# ALSN_v2.net
KiCad netlist of a schematic drawn in EAGLE
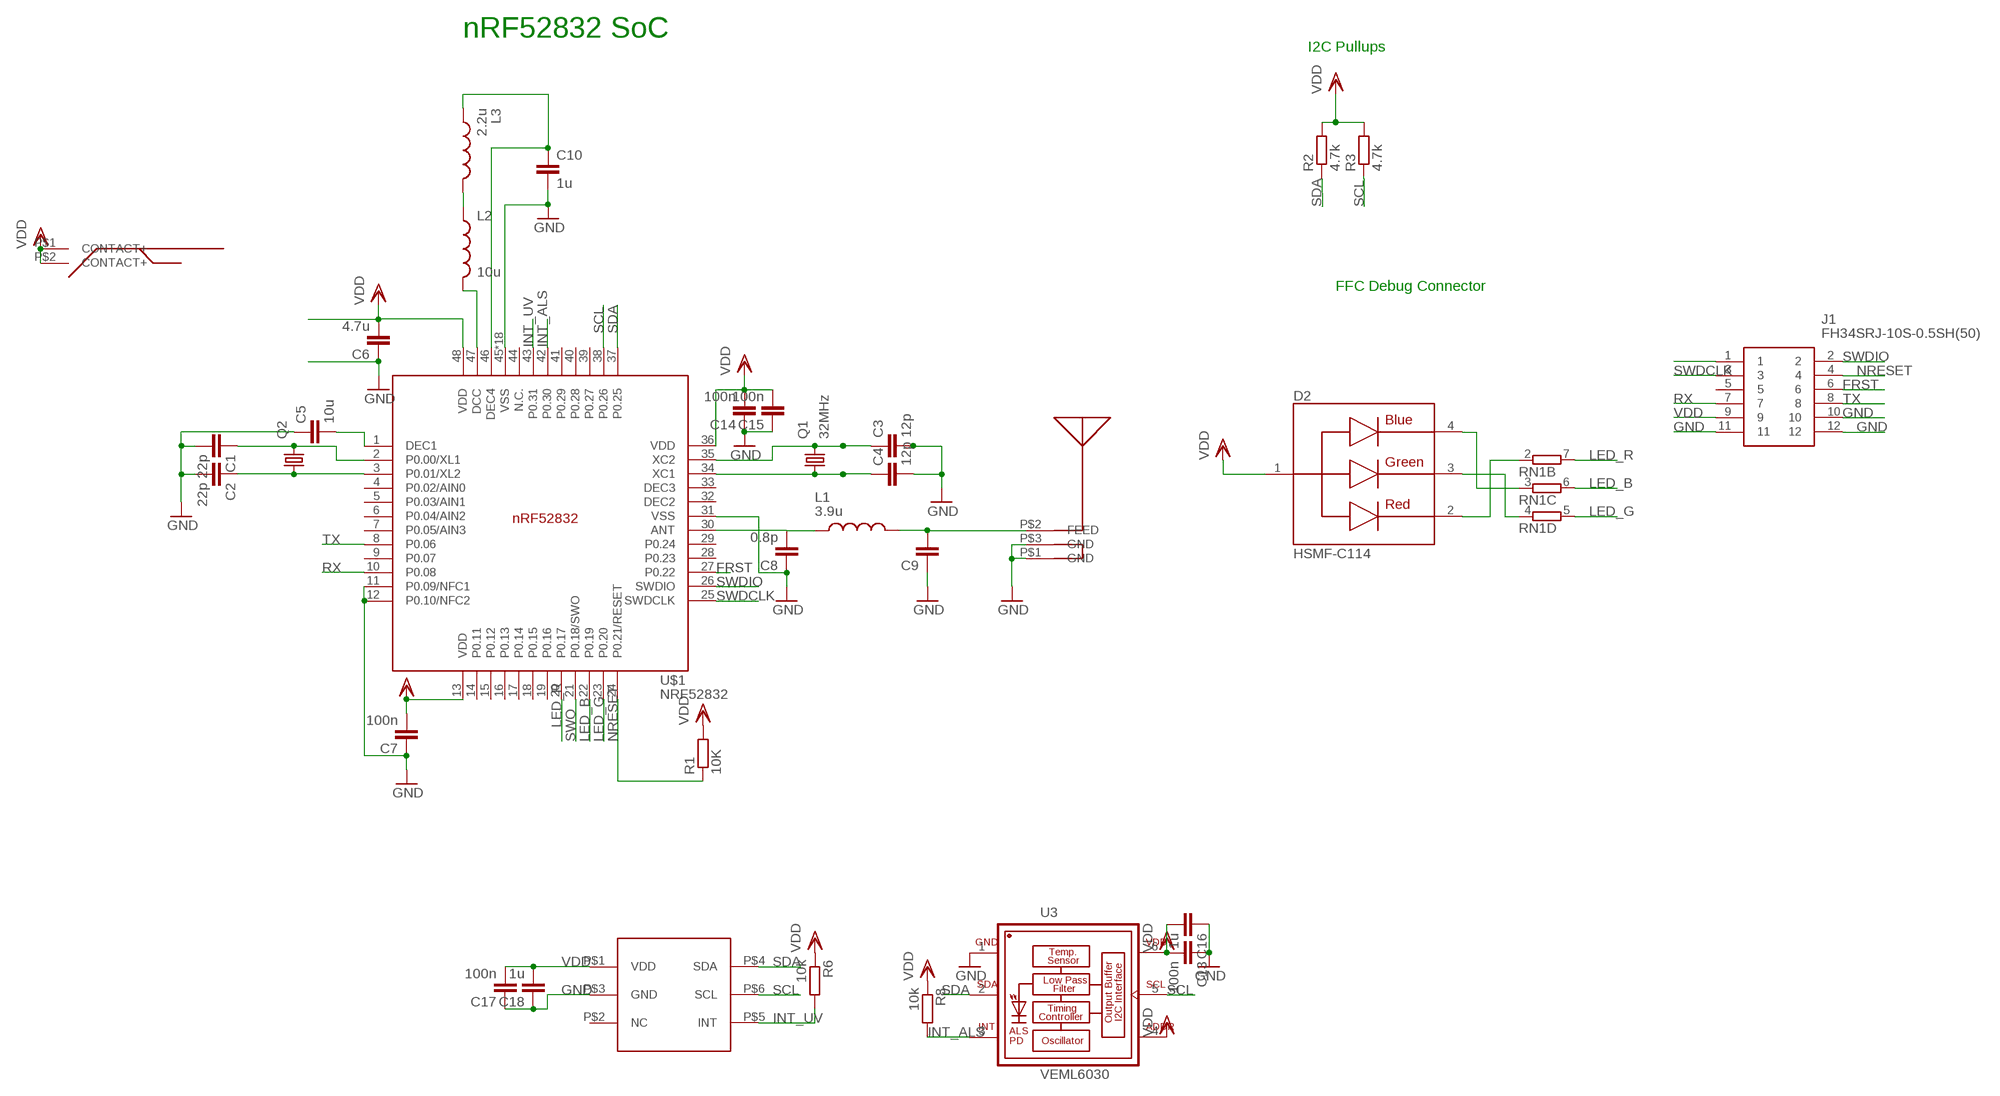
[diagram p0: schematic, sheet 1]

(export (version "E")
  (design (tool "Eeschema 10.0.6"))
  (components
    (comp (ref "C1")
      (value "22p")
      (footprint "eagle-import:C0402")
      (libsource (lib "eagle-import") (part "CC0402"))
    )
    (comp (ref "C2")
      (value "22p")
      (footprint "eagle-import:C0402")
      (libsource (lib "eagle-import") (part "CC0402"))
    )
    (comp (ref "C3")
      (value "12p")
      (footprint "eagle-import:C0402")
      (libsource (lib "eagle-import") (part "CC0402"))
    )
    (comp (ref "C4")
      (value "12p")
      (footprint "eagle-import:C0402")
      (libsource (lib "eagle-import") (part "CC0402"))
    )
    (comp (ref "C5")
      (value "10u")
      (footprint "eagle-import:C0402")
      (libsource (lib "eagle-import") (part "CC0402"))
    )
    (comp (ref "C6")
      (value "4.7u")
      (footprint "eagle-import:C0402")
      (libsource (lib "eagle-import") (part "CC0402"))
    )
    (comp (ref "C7")
      (value "100n")
      (footprint "eagle-import:C0603R")
      (libsource (lib "eagle-import") (part "CC0603R"))
    )
    (comp (ref "C8")
      (value "0.8p")
      (footprint "eagle-import:C0402")
      (libsource (lib "eagle-import") (part "CC0402"))
    )
    (comp (ref "C9")
      (value "1.2p")
      (footprint "eagle-import:C0402")
      (libsource (lib "eagle-import") (part "CC0402"))
    )
    (comp (ref "C10")
      (value "1u")
      (footprint "eagle-import:C0402")
      (libsource (lib "eagle-import") (part "CC0402"))
    )
    (comp (ref "C13")
      (value "100n")
      (footprint "eagle-import:C0402")
      (libsource (lib "eagle-import") (part "CC0402"))
    )
    (comp (ref "C14")
      (value "100n")
      (footprint "eagle-import:C0402")
      (libsource (lib "eagle-import") (part "CC0402"))
    )
    (comp (ref "C15")
      (value "100n")
      (footprint "eagle-import:C0402")
      (libsource (lib "eagle-import") (part "CC0402"))
    )
    (comp (ref "C16")
      (value "1u")
      (footprint "eagle-import:C0402")
      (libsource (lib "eagle-import") (part "CC0402"))
    )
    (comp (ref "C17")
      (value "100n")
      (footprint "eagle-import:C0402")
      (libsource (lib "eagle-import") (part "CC0402"))
    )
    (comp (ref "C18")
      (value "1u")
      (footprint "eagle-import:C0402")
      (libsource (lib "eagle-import") (part "CC0402"))
    )
    (comp (ref "D2")
      (value "HSMF-C114")
      (footprint "eagle-import:DIOSC160X150X35-4N")
      (fields (field (name "MF") "Broadcom Limited"))
      (libsource (lib "eagle-import") (part "HSMF-C114"))
    )
    (comp (ref "J1")
      (value "FH34SRJ-10S-0.5SH(50)")
      (footprint "eagle-import:FH34SRJ10S05SH50")
      (fields (field (name "MF") "Hirose Connector"))
      (libsource (lib "eagle-import") (part "FH34SRJ-10S-0.5SH(50)"))
    )
    (comp (ref "L1")
      (value "3.9u")
      (footprint "eagle-import:INDC0402X26N")
      (fields (field (name "MF") "TDK") (field (name "MP") "MHQ0402P7N5JT000"))
      (libsource (lib "eagle-import") (part "MHQ0402P7N5JT000"))
    )
    (comp (ref "L2")
      (value "10u")
      (footprint "eagle-import:L0603")
      (libsource (lib "eagle-import") (part "INDUCTOR"))
    )
    (comp (ref "L3")
      (value "2.2u")
      (footprint "eagle-import:INDC0402X26N")
      (fields (field (name "MF") "TDK") (field (name "MP") "MHQ0402P7N5JT000"))
      (libsource (lib "eagle-import") (part "MHQ0402P7N5JT000"))
    )
    (comp (ref "Q1")
      (value "32MHz")
      (footprint "eagle-import:2.0X1.6_KX-5")
      (libsource (lib "eagle-import") (part "KX-5"))
    )
    (comp (ref "Q2")
      (value "KX-327-RT")
      (footprint "eagle-import:2.0X1.2")
      (libsource (lib "eagle-import") (part "KX-327-RT"))
    )
    (comp (ref "R1")
      (value "10K")
      (footprint "eagle-import:R0402")
      (libsource (lib "eagle-import") (part "RR0402"))
    )
    (comp (ref "R2")
      (value "4.7k")
      (footprint "eagle-import:R0402")
      (libsource (lib "eagle-import") (part "RR0402"))
    )
    (comp (ref "R3")
      (value "4.7k")
      (footprint "eagle-import:R0402")
      (libsource (lib "eagle-import") (part "RR0402"))
    )
    (comp (ref "R6")
      (value "10k")
      (footprint "eagle-import:R0402")
      (libsource (lib "eagle-import") (part "RR0402"))
    )
    (comp (ref "R8")
      (value "10k")
      (footprint "eagle-import:R0402")
      (libsource (lib "eagle-import") (part "RR0402"))
    )
    (comp (ref "RN1")
      (value "4R-N0402ARV341")
      (footprint "eagle-import:4X0402ARV341")
      (libsource (lib "eagle-import") (part "4R-N0402ARV341"))
    )
    (comp (ref "U$1")
      (value "NRF52832")
      (footprint "eagle-import:QFN40P600X600X90-48_N")
      (libsource (lib "eagle-import") (part "NRF52832"))
    )
    (comp (ref "U$2")
      (value "CR2032-THT")
      (footprint "eagle-import:CR2032-THT")
      (libsource (lib "eagle-import") (part "CR2032-THT"))
    )
    (comp (ref "U$3")
      (value "LTR-390UV")
      (footprint "eagle-import:LTR-390UV")
      (libsource (lib "eagle-import") (part "LTR-390UV"))
    )
    (comp (ref "U$4")
      (value "CHIPANTENNAL2")
      (footprint "eagle-import:CHIPANTENNAL2")
      (libsource (lib "eagle-import") (part "CHIPANTENNAL2"))
    )
    (comp (ref "U3")
      (value "VEML6030")
      (footprint "eagle-import:VISHAY_VEML6030_2X2X0.87")
      (fields (field (name "MF") "Vishay"))
      (libsource (lib "eagle-import") (part "VEML6030"))
    )
  )
  (nets
    (net (code "1") (name "/FRST") (class "Default")
      (node (ref "J1") (pin "6") (pinfunction "6_6") (pintype "bidirectional"))
      (node (ref "U$1") (pin "27") (pinfunction "P0.22_27") (pintype "bidirectional"))
    )
    (net (code "2") (name "/INT_ALS") (class "Default")
      (node (ref "R8") (pin "2") (pinfunction "2_2") (pintype "passive"))
      (node (ref "U$1") (pin "42") (pinfunction "P0.30_42") (pintype "bidirectional"))
      (node (ref "U3") (pin "3") (pinfunction "INT_3") (pintype "output"))
    )
    (net (code "3") (name "/INT_UV") (class "Default")
      (node (ref "R6") (pin "2") (pinfunction "2_2") (pintype "passive"))
      (node (ref "U$1") (pin "43") (pinfunction "P0.31_43") (pintype "bidirectional"))
      (node (ref "U$3") (pin "P$5") (pinfunction "INT_P$5") (pintype "bidirectional"))
    )
    (net (code "4") (name "/LED_B") (class "Default")
      (node (ref "RN1") (pin "6") (pinfunction "2_6") (pintype "passive"))
      (node (ref "U$1") (pin "22") (pinfunction "P0.19_22") (pintype "bidirectional"))
    )
    (net (code "5") (name "/LED_G") (class "Default")
      (node (ref "RN1") (pin "5") (pinfunction "2_5") (pintype "passive"))
      (node (ref "U$1") (pin "23") (pinfunction "P0.20_23") (pintype "bidirectional"))
    )
    (net (code "6") (name "/LED_R") (class "Default")
      (node (ref "RN1") (pin "7") (pinfunction "2_7") (pintype "passive"))
      (node (ref "U$1") (pin "20") (pinfunction "P0.17_20") (pintype "bidirectional"))
    )
    (net (code "7") (name "/NRESET") (class "Default")
      (node (ref "J1") (pin "4") (pinfunction "4_4") (pintype "bidirectional"))
      (node (ref "R1") (pin "1") (pinfunction "1_1") (pintype "passive"))
      (node (ref "U$1") (pin "24") (pinfunction "P0.21/RESET_24") (pintype "bidirectional"))
    )
    (net (code "8") (name "/RX") (class "Default")
      (node (ref "J1") (pin "7") (pinfunction "7_7") (pintype "bidirectional"))
      (node (ref "U$1") (pin "10") (pinfunction "P0.08_10") (pintype "bidirectional"))
    )
    (net (code "9") (name "/SCL") (class "Default")
      (node (ref "R3") (pin "1") (pinfunction "1_1") (pintype "passive"))
      (node (ref "U$1") (pin "38") (pinfunction "P0.26_38") (pintype "bidirectional"))
      (node (ref "U$3") (pin "P$6") (pinfunction "SCL_P$6") (pintype "bidirectional"))
      (node (ref "U3") (pin "5") (pinfunction "SCL_5") (pintype "input"))
    )
    (net (code "10") (name "/SDA") (class "Default")
      (node (ref "R2") (pin "1") (pinfunction "1_1") (pintype "passive"))
      (node (ref "U$1") (pin "37") (pinfunction "P0.25_37") (pintype "bidirectional"))
      (node (ref "U$3") (pin "P$4") (pinfunction "SDA_P$4") (pintype "bidirectional"))
      (node (ref "U3") (pin "2") (pinfunction "SDA_2") (pintype "bidirectional"))
    )
    (net (code "11") (name "/SWDCLK") (class "Default")
      (node (ref "J1") (pin "3") (pinfunction "3_3") (pintype "bidirectional"))
      (node (ref "U$1") (pin "25") (pinfunction "SWDCLK_25") (pintype "input"))
    )
    (net (code "12") (name "/SWDIO") (class "Default")
      (node (ref "J1") (pin "2") (pinfunction "2_2") (pintype "bidirectional"))
      (node (ref "U$1") (pin "26") (pinfunction "SWDIO_26") (pintype "bidirectional"))
    )
    (net (code "13") (name "/SWO") (class "Default")
      (node (ref "U$1") (pin "21") (pinfunction "P0.18/SWO_21") (pintype "bidirectional"))
    )
    (net (code "14") (name "/TX") (class "Default")
      (node (ref "J1") (pin "8") (pinfunction "8_8") (pintype "bidirectional"))
      (node (ref "U$1") (pin "8") (pinfunction "P0.06_8") (pintype "bidirectional"))
    )
    (net (code "15") (name "GND") (class "Default")
      (node (ref "C1") (pin "2") (pinfunction "2_2") (pintype "passive"))
      (node (ref "C10") (pin "2") (pinfunction "2_2") (pintype "passive"))
      (node (ref "C13") (pin "1") (pinfunction "1_1") (pintype "passive"))
      (node (ref "C14") (pin "1") (pinfunction "1_1") (pintype "passive"))
      (node (ref "C15") (pin "1") (pinfunction "1_1") (pintype "passive"))
      (node (ref "C16") (pin "1") (pinfunction "1_1") (pintype "passive"))
      (node (ref "C17") (pin "1") (pinfunction "1_1") (pintype "passive"))
      (node (ref "C18") (pin "1") (pinfunction "1_1") (pintype "passive"))
      (node (ref "C2") (pin "2") (pinfunction "2_2") (pintype "passive"))
      (node (ref "C3") (pin "2") (pinfunction "2_2") (pintype "passive"))
      (node (ref "C4") (pin "2") (pinfunction "2_2") (pintype "passive"))
      (node (ref "C5") (pin "1") (pinfunction "1_1") (pintype "passive"))
      (node (ref "C6") (pin "1") (pinfunction "1_1") (pintype "passive"))
      (node (ref "C7") (pin "1") (pinfunction "1_1") (pintype "passive"))
      (node (ref "C8") (pin "1") (pinfunction "1_1") (pintype "passive"))
      (node (ref "C9") (pin "1") (pinfunction "1_1") (pintype "passive"))
      (node (ref "J1") (pin "10") (pinfunction "10_10") (pintype "bidirectional"))
      (node (ref "J1") (pin "11") (pinfunction "11_11") (pintype "bidirectional"))
      (node (ref "J1") (pin "12") (pinfunction "12_12") (pintype "bidirectional"))
      (node (ref "U$1") (pin "11") (pinfunction "P0.09/NFC1_11") (pintype "bidirectional"))
      (node (ref "U$1") (pin "12") (pinfunction "P0.10/NFC2_12") (pintype "bidirectional"))
      (node (ref "U$1") (pin "31") (pinfunction "VSS_31") (pintype "bidirectional"))
      (node (ref "U$1") (pin "45") (pinfunction "VSS_45") (pintype "power_in"))
      (node (ref "U$1") (pin "PAD") (pinfunction "VSS_PAD") (pintype "power_in"))
      (node (ref "U$1") (pin "PAD@VIA01") (pinfunction "VSS_PAD@VIA01") (pintype "power_in"))
      (node (ref "U$1") (pin "PAD@VIA02") (pinfunction "VSS_PAD@VIA02") (pintype "power_in"))
      (node (ref "U$1") (pin "PAD@VIA03") (pinfunction "VSS_PAD@VIA03") (pintype "power_in"))
      (node (ref "U$1") (pin "PAD@VIA04") (pinfunction "VSS_PAD@VIA04") (pintype "power_in"))
      (node (ref "U$1") (pin "PAD@VIA05") (pinfunction "VSS_PAD@VIA05") (pintype "power_in"))
      (node (ref "U$1") (pin "PAD@VIA06") (pinfunction "VSS_PAD@VIA06") (pintype "power_in"))
      (node (ref "U$1") (pin "PAD@VIA07") (pinfunction "VSS_PAD@VIA07") (pintype "power_in"))
      (node (ref "U$1") (pin "PAD@VIA08") (pinfunction "VSS_PAD@VIA08") (pintype "power_in"))
      (node (ref "U$1") (pin "PAD@VIA09") (pinfunction "VSS_PAD@VIA09") (pintype "power_in"))
      (node (ref "U$1") (pin "PAD@VIA10") (pinfunction "VSS_PAD@VIA10") (pintype "power_in"))
      (node (ref "U$1") (pin "PAD@VIA11") (pinfunction "VSS_PAD@VIA11") (pintype "power_in"))
      (node (ref "U$1") (pin "PAD@VIA12") (pinfunction "VSS_PAD@VIA12") (pintype "power_in"))
      (node (ref "U$1") (pin "PAD@VIA13") (pinfunction "VSS_PAD@VIA13") (pintype "power_in"))
      (node (ref "U$1") (pin "PAD@VIA14") (pinfunction "VSS_PAD@VIA14") (pintype "power_in"))
      (node (ref "U$1") (pin "PAD@VIA15") (pinfunction "VSS_PAD@VIA15") (pintype "power_in"))
      (node (ref "U$1") (pin "PAD@VIA16") (pinfunction "VSS_PAD@VIA16") (pintype "power_in"))
      (node (ref "U$3") (pin "P$3") (pinfunction "GND_P$3") (pintype "bidirectional"))
      (node (ref "U$4") (pin "P$1") (pinfunction "GND_P$1") (pintype "bidirectional"))
      (node (ref "U$4") (pin "P$3") (pinfunction "GND_P$3") (pintype "bidirectional"))
      (node (ref "U3") (pin "1") (pinfunction "GND_1") (pintype "power_in"))
    )
    (net (code "16") (name "Net-(L2-Pad1)") (class "Default")
      (node (ref "L2") (pin "1") (pinfunction "1_1") (pintype "passive"))
      (node (ref "L3") (pin "2") (pinfunction "2_2") (pintype "passive"))
    )
    (net (code "17") (name "Net-(Q1-2)") (class "Default")
      (node (ref "C3") (pin "1") (pinfunction "1_1") (pintype "passive"))
      (node (ref "Q1") (pin "3") (pinfunction "2_3") (pintype "passive"))
      (node (ref "U$1") (pin "35") (pinfunction "XC2_35") (pintype "output"))
    )
    (net (code "18") (name "Net-(RN1B-1)") (class "Default")
      (node (ref "D2") (pin "2") (pinfunction "2_2") (pintype "passive"))
      (node (ref "RN1") (pin "2") (pinfunction "1_2") (pintype "passive"))
    )
    (net (code "19") (name "Net-(RN1C-1)") (class "Default")
      (node (ref "D2") (pin "4") (pinfunction "4_4") (pintype "passive"))
      (node (ref "RN1") (pin "3") (pinfunction "1_3") (pintype "passive"))
    )
    (net (code "20") (name "Net-(RN1D-1)") (class "Default")
      (node (ref "D2") (pin "3") (pinfunction "3_3") (pintype "passive"))
      (node (ref "RN1") (pin "4") (pinfunction "1_4") (pintype "passive"))
    )
    (net (code "21") (name "Net-(U$1-ANT)") (class "Default")
      (node (ref "C8") (pin "2") (pinfunction "2_2") (pintype "passive"))
      (node (ref "L1") (pin "1") (pinfunction "1_1") (pintype "passive"))
      (node (ref "U$1") (pin "30") (pinfunction "ANT_30") (pintype "bidirectional"))
    )
    (net (code "22") (name "Net-(U$1-DCC)") (class "Default")
      (node (ref "L2") (pin "2") (pinfunction "2_2") (pintype "passive"))
      (node (ref "U$1") (pin "47") (pinfunction "DCC_47") (pintype "output"))
    )
    (net (code "23") (name "Net-(U$1-DEC1)") (class "Default")
      (node (ref "C5") (pin "2") (pinfunction "2_2") (pintype "passive"))
      (node (ref "U$1") (pin "1") (pinfunction "DEC1_1") (pintype "power_in"))
    )
    (net (code "24") (name "Net-(U$1-DEC4)") (class "Default")
      (node (ref "C10") (pin "1") (pinfunction "1_1") (pintype "passive"))
      (node (ref "L3") (pin "1") (pinfunction "1_1") (pintype "passive"))
      (node (ref "U$1") (pin "46") (pinfunction "DEC4_46") (pintype "power_in"))
    )
    (net (code "25") (name "Net-(U$1-P0.00{slash}XL1)") (class "Default")
      (node (ref "C1") (pin "1") (pinfunction "1_1") (pintype "passive"))
      (node (ref "Q2") (pin "2") (pinfunction "2_2") (pintype "passive"))
      (node (ref "U$1") (pin "2") (pinfunction "P0.00/XL1_2") (pintype "bidirectional"))
    )
    (net (code "26") (name "Net-(U$1-P0.01{slash}XL2)") (class "Default")
      (node (ref "C2") (pin "1") (pinfunction "1_1") (pintype "passive"))
      (node (ref "Q2") (pin "1") (pinfunction "1_1") (pintype "passive"))
      (node (ref "U$1") (pin "3") (pinfunction "P0.01/XL2_3") (pintype "bidirectional"))
    )
    (net (code "27") (name "Net-(U$1-XC1)") (class "Default")
      (node (ref "C4") (pin "1") (pinfunction "1_1") (pintype "passive"))
      (node (ref "Q1") (pin "1") (pinfunction "1_1") (pintype "passive"))
      (node (ref "U$1") (pin "34") (pinfunction "XC1_34") (pintype "input"))
    )
    (net (code "28") (name "Net-(U$4-FEED)") (class "Default")
      (node (ref "C9") (pin "2") (pinfunction "2_2") (pintype "passive"))
      (node (ref "L1") (pin "2") (pinfunction "2_2") (pintype "passive"))
      (node (ref "U$4") (pin "P$2") (pinfunction "FEED_P$2") (pintype "bidirectional"))
    )
    (net (code "29") (name "VDD") (class "Default")
      (node (ref "C13") (pin "2") (pinfunction "2_2") (pintype "passive"))
      (node (ref "C14") (pin "2") (pinfunction "2_2") (pintype "passive"))
      (node (ref "C15") (pin "2") (pinfunction "2_2") (pintype "passive"))
      (node (ref "C16") (pin "2") (pinfunction "2_2") (pintype "passive"))
      (node (ref "C17") (pin "2") (pinfunction "2_2") (pintype "passive"))
      (node (ref "C18") (pin "2") (pinfunction "2_2") (pintype "passive"))
      (node (ref "C6") (pin "2") (pinfunction "2_2") (pintype "passive"))
      (node (ref "C7") (pin "2") (pinfunction "2_2") (pintype "passive"))
      (node (ref "D2") (pin "1") (pinfunction "1_1") (pintype "passive"))
      (node (ref "J1") (pin "9") (pinfunction "9_9") (pintype "bidirectional"))
      (node (ref "R1") (pin "2") (pinfunction "2_2") (pintype "passive"))
      (node (ref "R2") (pin "2") (pinfunction "2_2") (pintype "passive"))
      (node (ref "R3") (pin "2") (pinfunction "2_2") (pintype "passive"))
      (node (ref "R6") (pin "1") (pinfunction "1_1") (pintype "passive"))
      (node (ref "R8") (pin "1") (pinfunction "1_1") (pintype "passive"))
      (node (ref "U$1") (pin "13") (pinfunction "VDD_13") (pintype "power_in"))
      (node (ref "U$1") (pin "36") (pinfunction "VDD_36") (pintype "power_in"))
      (node (ref "U$1") (pin "48") (pinfunction "VDD_48") (pintype "power_in"))
      (node (ref "U$2") (pin "P$1") (pinfunction "CONTACT+_P$1") (pintype "bidirectional"))
      (node (ref "U$2") (pin "P$2") (pinfunction "CONTACT+_P$2") (pintype "bidirectional"))
      (node (ref "U$3") (pin "P$1") (pinfunction "VDD_P$1") (pintype "bidirectional"))
      (node (ref "U3") (pin "4") (pinfunction "ADDR_4") (pintype "bidirectional"))
      (node (ref "U3") (pin "6") (pinfunction "VDD_6") (pintype "power_in"))
    )
    (net (code "30") (name "unconnected-(J1-Pad1)") (class "Default")
      (node (ref "J1") (pin "1") (pinfunction "1_1") (pintype "bidirectional"))
    )
    (net (code "31") (name "unconnected-(J1-Pad5)") (class "Default")
      (node (ref "J1") (pin "5") (pinfunction "5_5") (pintype "bidirectional"))
    )
    (net (code "32") (name "unconnected-(U$1-DEC2-Pad32)") (class "Default")
      (node (ref "U$1") (pin "32") (pinfunction "DEC2_32") (pintype "bidirectional"))
    )
    (net (code "33") (name "unconnected-(U$1-DEC3-Pad33)") (class "Default")
      (node (ref "U$1") (pin "33") (pinfunction "DEC3_33") (pintype "bidirectional"))
    )
    (net (code "34") (name "unconnected-(U$1-N.C.-Pad44)") (class "Default")
      (node (ref "U$1") (pin "44") (pinfunction "N.C._44") (pintype "no_connect"))
    )
    (net (code "35") (name "unconnected-(U$1-P0.02{slash}AIN0-Pad4)") (class "Default")
      (node (ref "U$1") (pin "4") (pinfunction "P0.02/AIN0_4") (pintype "bidirectional"))
    )
    (net (code "36") (name "unconnected-(U$1-P0.03{slash}AIN1-Pad5)") (class "Default")
      (node (ref "U$1") (pin "5") (pinfunction "P0.03/AIN1_5") (pintype "bidirectional"))
    )
    (net (code "37") (name "unconnected-(U$1-P0.04{slash}AIN2-Pad6)") (class "Default")
      (node (ref "U$1") (pin "6") (pinfunction "P0.04/AIN2_6") (pintype "bidirectional"))
    )
    (net (code "38") (name "unconnected-(U$1-P0.05{slash}AIN3-Pad7)") (class "Default")
      (node (ref "U$1") (pin "7") (pinfunction "P0.05/AIN3_7") (pintype "bidirectional"))
    )
    (net (code "39") (name "unconnected-(U$1-P0.07-Pad9)") (class "Default")
      (node (ref "U$1") (pin "9") (pinfunction "P0.07_9") (pintype "bidirectional"))
    )
    (net (code "40") (name "unconnected-(U$1-P0.11-Pad14)") (class "Default")
      (node (ref "U$1") (pin "14") (pinfunction "P0.11_14") (pintype "bidirectional"))
    )
    (net (code "41") (name "unconnected-(U$1-P0.12-Pad15)") (class "Default")
      (node (ref "U$1") (pin "15") (pinfunction "P0.12_15") (pintype "bidirectional"))
    )
    (net (code "42") (name "unconnected-(U$1-P0.13-Pad16)") (class "Default")
      (node (ref "U$1") (pin "16") (pinfunction "P0.13_16") (pintype "bidirectional"))
    )
    (net (code "43") (name "unconnected-(U$1-P0.14-Pad17)") (class "Default")
      (node (ref "U$1") (pin "17") (pinfunction "P0.14_17") (pintype "bidirectional"))
    )
    (net (code "44") (name "unconnected-(U$1-P0.15-Pad18)") (class "Default")
      (node (ref "U$1") (pin "18") (pinfunction "P0.15_18") (pintype "bidirectional"))
    )
    (net (code "45") (name "unconnected-(U$1-P0.16-Pad19)") (class "Default")
      (node (ref "U$1") (pin "19") (pinfunction "P0.16_19") (pintype "bidirectional"))
    )
    (net (code "46") (name "unconnected-(U$1-P0.23-Pad28)") (class "Default")
      (node (ref "U$1") (pin "28") (pinfunction "P0.23_28") (pintype "bidirectional"))
    )
    (net (code "47") (name "unconnected-(U$1-P0.24-Pad29)") (class "Default")
      (node (ref "U$1") (pin "29") (pinfunction "P0.24_29") (pintype "bidirectional"))
    )
    (net (code "48") (name "unconnected-(U$1-P0.27-Pad39)") (class "Default")
      (node (ref "U$1") (pin "39") (pinfunction "P0.27_39") (pintype "bidirectional"))
    )
    (net (code "49") (name "unconnected-(U$1-P0.28-Pad40)") (class "Default")
      (node (ref "U$1") (pin "40") (pinfunction "P0.28_40") (pintype "bidirectional"))
    )
    (net (code "50") (name "unconnected-(U$1-P0.29-Pad41)") (class "Default")
      (node (ref "U$1") (pin "41") (pinfunction "P0.29_41") (pintype "bidirectional"))
    )
    (net (code "51") (name "unconnected-(U$3-NC-PadP$2)") (class "Default")
      (node (ref "U$3") (pin "P$2") (pinfunction "NC_P$2") (pintype "bidirectional"))
    )
  )
)
